# Main.net
KiCad netlist of a schematic drawn in Altium Designer
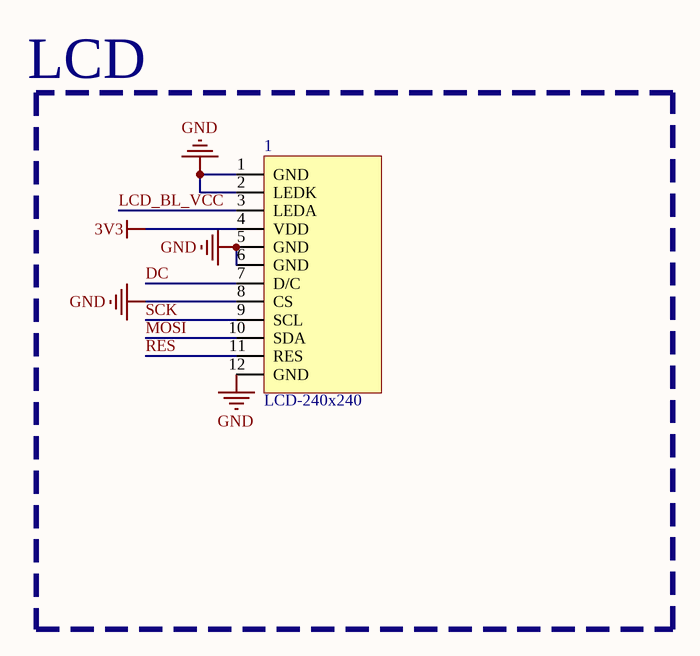
[diagram p0: Main.SchDoc]

(export (version "E")
  (design (tool "Eeschema 10.0.6"))
  (components
    (comp (ref "1")
      (value "LCD-240x240")
      (footprint "LCD-240x240-NoHole")
      (description "显示屏")
      (libsource (lib "mLib") (part "LCD-240x240"))
    )
  )
  (nets
    (net (code "1") (name "/DC") (class "Default")
      (node (ref "1") (pin "7") (pinfunction "D/C_7") (pintype "passive"))
    )
    (net (code "2") (name "/LCD_BL_VCC") (class "Default")
      (node (ref "1") (pin "3") (pinfunction "LEDA_3") (pintype "passive"))
    )
    (net (code "3") (name "/MOSI") (class "Default")
      (node (ref "1") (pin "10") (pinfunction "SDA_10") (pintype "passive"))
    )
    (net (code "4") (name "/RES") (class "Default")
      (node (ref "1") (pin "11") (pinfunction "RES_11") (pintype "passive"))
    )
    (net (code "5") (name "/SCK") (class "Default")
      (node (ref "1") (pin "9") (pinfunction "SCL_9") (pintype "passive"))
    )
    (net (code "6") (name "3V3") (class "Default")
      (node (ref "1") (pin "4") (pinfunction "VDD_4") (pintype "passive"))
    )
    (net (code "7") (name "GND") (class "Default")
      (node (ref "1") (pin "1") (pinfunction "GND_1") (pintype "passive"))
      (node (ref "1") (pin "12") (pinfunction "GND_12") (pintype "passive"))
      (node (ref "1") (pin "2") (pinfunction "LEDK_2") (pintype "passive"))
      (node (ref "1") (pin "5") (pinfunction "GND_5") (pintype "passive"))
      (node (ref "1") (pin "6") (pinfunction "GND_6") (pintype "passive"))
      (node (ref "1") (pin "8") (pinfunction "CS_8") (pintype "passive"))
    )
  )
)
